# MCU_Headers.net
KiCad netlist of a schematic drawn in Altium Designer
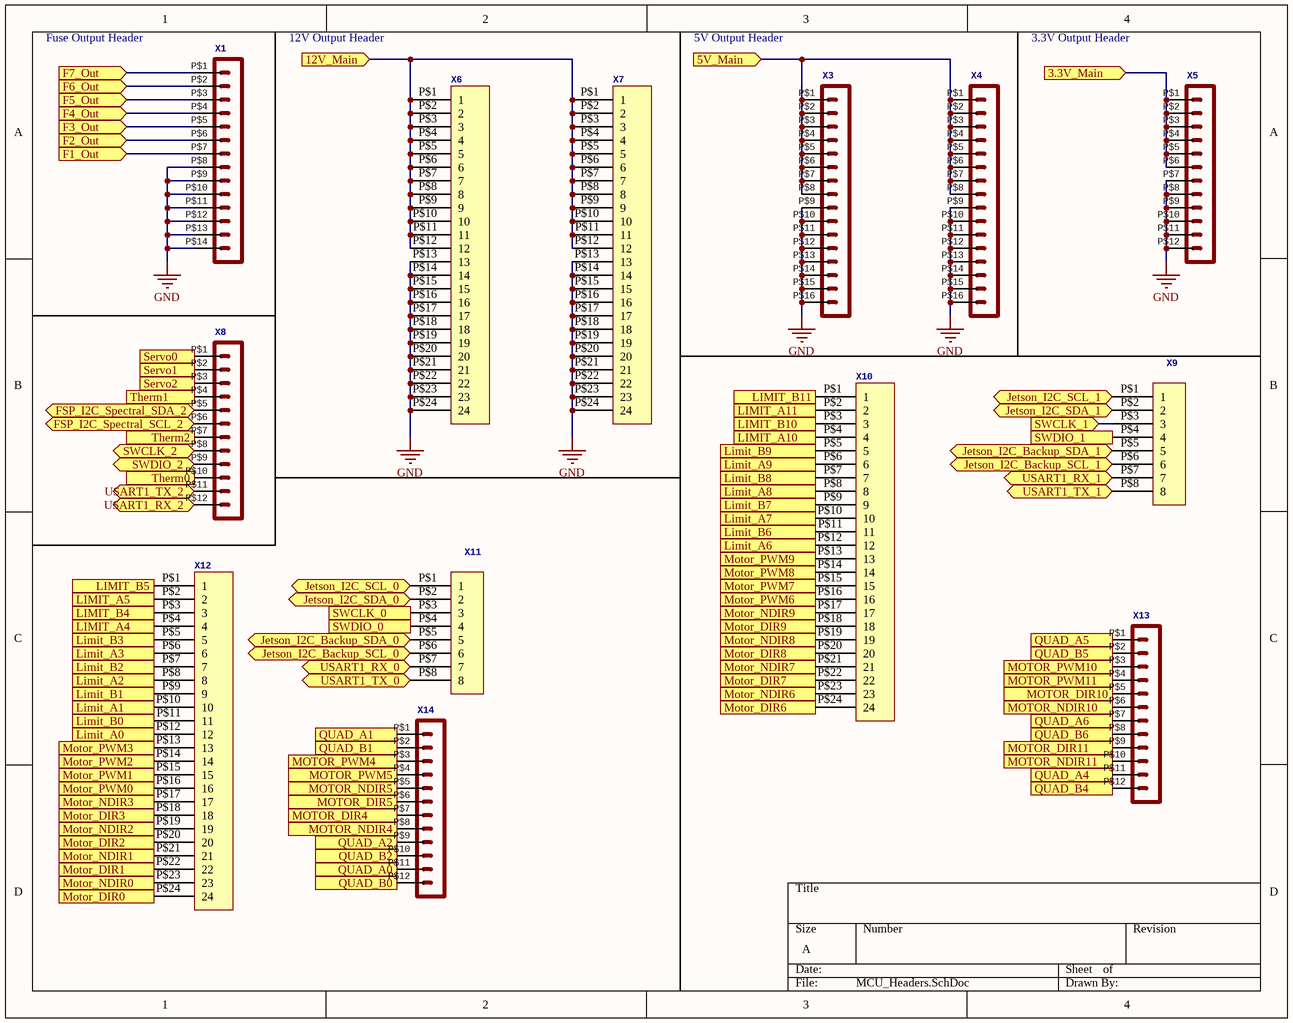
[diagram p0: MCU_Headers.SchDoc]

(export (version "E")
  (design (tool "Eeschema 10.0.6"))
  (components
    (comp (ref "X1")
      (value "Molex - Micro-Fit 3.0 Series connector,  3.00mm (0.118\") pitch header, 14 positions.")
      (footprint "43045-1412")
      (libsource (lib "Molex Microfit") (part "HEADER_POS14_?43045-1412"))
    )
    (comp (ref "X3")
      (value "Molex - Micro-Fit 3.0 Series connector,  3.00mm (0.118\") pitch header, 16 positions.")
      (footprint "43045-1612")
      (libsource (lib "Molex Microfit") (part "HEADER_POS16_?43045-1612"))
    )
    (comp (ref "X4")
      (value "Molex - Micro-Fit 3.0 Series connector,  3.00mm (0.118\") pitch header, 16 positions.")
      (footprint "43045-1612")
      (libsource (lib "Molex Microfit") (part "HEADER_POS16_?43045-1612"))
    )
    (comp (ref "X5")
      (value "Molex - Micro-Fit 3.0 Series connector,  3.00mm (0.118\") pitch header, 12 positions.")
      (footprint "43045-1212")
      (libsource (lib "Molex Microfit") (part "HEADER_POS12_?43045-1212"))
    )
    (comp (ref "X6")
      (value "Molex 43045-2412")
      (footprint "43045-2412")
      (libsource (lib "Molex Microfit") (part "Micro-Fit Molex 24 Pin Vertical"))
    )
    (comp (ref "X7")
      (value "Molex 43045-2412")
      (footprint "43045-2412")
      (libsource (lib "Molex Microfit") (part "Micro-Fit Molex 24 Pin Vertical"))
    )
    (comp (ref "X8")
      (value "Molex - Micro-Fit 3.0 Series connector,  3.00mm (0.118\") pitch header, 12 positions.")
      (footprint "43045-1212")
      (libsource (lib "Molex Microfit") (part "HEADER_POS12_?43045-1212"))
    )
    (comp (ref "X9")
      (value "Molex 43045-0812")
      (footprint "43045-0812")
      (libsource (lib "Molex Microfit") (part "Micro-Fit Molex 8 Pin 2 Row Vertical"))
    )
    (comp (ref "X10")
      (value "Molex 43045-2412")
      (footprint "43045-2412")
      (libsource (lib "Molex Microfit") (part "Micro-Fit Molex 24 Pin Vertical"))
    )
    (comp (ref "X11")
      (value "Molex 43045-0812")
      (footprint "43045-0812")
      (libsource (lib "Molex Microfit") (part "Micro-Fit Molex 8 Pin 2 Row Vertical"))
    )
    (comp (ref "X12")
      (value "Molex 43045-2412")
      (footprint "43045-2412")
      (libsource (lib "Molex Microfit") (part "Micro-Fit Molex 24 Pin Vertical"))
    )
    (comp (ref "X13")
      (value "Molex - Micro-Fit 3.0 Series connector,  3.00mm (0.118\") pitch header, 12 positions.")
      (footprint "43045-1212")
      (libsource (lib "Molex Microfit") (part "HEADER_POS12_?43045-1212"))
    )
    (comp (ref "X14")
      (value "Molex - Micro-Fit 3.0 Series connector,  3.00mm (0.118\") pitch header, 12 positions.")
      (footprint "43045-1212")
      (libsource (lib "Molex Microfit") (part "HEADER_POS12_?43045-1212"))
    )
  )
  (nets
    (net (code "1") (name "/3.3V_Main") (class "Default")
      (node (ref "X5") (pin "P$1") (pinfunction "1_P$1") (pintype "passive"))
      (node (ref "X5") (pin "P$2") (pinfunction "2_P$2") (pintype "passive"))
      (node (ref "X5") (pin "P$3") (pinfunction "3_P$3") (pintype "passive"))
      (node (ref "X5") (pin "P$4") (pinfunction "4_P$4") (pintype "passive"))
      (node (ref "X5") (pin "P$5") (pinfunction "5_P$5") (pintype "passive"))
      (node (ref "X5") (pin "P$6") (pinfunction "6_P$6") (pintype "passive"))
    )
    (net (code "2") (name "/5V_Main") (class "Default")
      (node (ref "X3") (pin "P$1") (pinfunction "1_P$1") (pintype "passive"))
      (node (ref "X3") (pin "P$2") (pinfunction "2_P$2") (pintype "passive"))
      (node (ref "X3") (pin "P$3") (pinfunction "3_P$3") (pintype "passive"))
      (node (ref "X3") (pin "P$4") (pinfunction "4_P$4") (pintype "passive"))
      (node (ref "X3") (pin "P$5") (pinfunction "5_P$5") (pintype "passive"))
      (node (ref "X3") (pin "P$6") (pinfunction "6_P$6") (pintype "passive"))
      (node (ref "X3") (pin "P$7") (pinfunction "7_P$7") (pintype "passive"))
      (node (ref "X3") (pin "P$8") (pinfunction "8_P$8") (pintype "passive"))
      (node (ref "X4") (pin "P$1") (pinfunction "1_P$1") (pintype "passive"))
      (node (ref "X4") (pin "P$2") (pinfunction "2_P$2") (pintype "passive"))
      (node (ref "X4") (pin "P$3") (pinfunction "3_P$3") (pintype "passive"))
      (node (ref "X4") (pin "P$4") (pinfunction "4_P$4") (pintype "passive"))
      (node (ref "X4") (pin "P$5") (pinfunction "5_P$5") (pintype "passive"))
      (node (ref "X4") (pin "P$6") (pinfunction "6_P$6") (pintype "passive"))
      (node (ref "X4") (pin "P$7") (pinfunction "7_P$7") (pintype "passive"))
      (node (ref "X4") (pin "P$8") (pinfunction "8_P$8") (pintype "passive"))
    )
    (net (code "3") (name "/12V_Main") (class "Default")
      (node (ref "X6") (pin "P$1") (pinfunction "1_P$1") (pintype "passive"))
      (node (ref "X6") (pin "P$10") (pinfunction "10_P$10") (pintype "passive"))
      (node (ref "X6") (pin "P$11") (pinfunction "11_P$11") (pintype "passive"))
      (node (ref "X6") (pin "P$12") (pinfunction "12_P$12") (pintype "passive"))
      (node (ref "X6") (pin "P$2") (pinfunction "2_P$2") (pintype "passive"))
      (node (ref "X6") (pin "P$3") (pinfunction "3_P$3") (pintype "passive"))
      (node (ref "X6") (pin "P$4") (pinfunction "4_P$4") (pintype "passive"))
      (node (ref "X6") (pin "P$5") (pinfunction "5_P$5") (pintype "passive"))
      (node (ref "X6") (pin "P$6") (pinfunction "6_P$6") (pintype "passive"))
      (node (ref "X6") (pin "P$7") (pinfunction "7_P$7") (pintype "passive"))
      (node (ref "X6") (pin "P$8") (pinfunction "8_P$8") (pintype "passive"))
      (node (ref "X6") (pin "P$9") (pinfunction "9_P$9") (pintype "passive"))
      (node (ref "X7") (pin "P$1") (pinfunction "1_P$1") (pintype "passive"))
      (node (ref "X7") (pin "P$10") (pinfunction "10_P$10") (pintype "passive"))
      (node (ref "X7") (pin "P$11") (pinfunction "11_P$11") (pintype "passive"))
      (node (ref "X7") (pin "P$12") (pinfunction "12_P$12") (pintype "passive"))
      (node (ref "X7") (pin "P$2") (pinfunction "2_P$2") (pintype "passive"))
      (node (ref "X7") (pin "P$3") (pinfunction "3_P$3") (pintype "passive"))
      (node (ref "X7") (pin "P$4") (pinfunction "4_P$4") (pintype "passive"))
      (node (ref "X7") (pin "P$5") (pinfunction "5_P$5") (pintype "passive"))
      (node (ref "X7") (pin "P$6") (pinfunction "6_P$6") (pintype "passive"))
      (node (ref "X7") (pin "P$7") (pinfunction "7_P$7") (pintype "passive"))
      (node (ref "X7") (pin "P$8") (pinfunction "8_P$8") (pintype "passive"))
      (node (ref "X7") (pin "P$9") (pinfunction "9_P$9") (pintype "passive"))
    )
    (net (code "4") (name "/F1_Out") (class "Default")
      (node (ref "X1") (pin "P$7") (pinfunction "7_P$7") (pintype "passive"))
    )
    (net (code "5") (name "/F2_Out") (class "Default")
      (node (ref "X1") (pin "P$6") (pinfunction "6_P$6") (pintype "passive"))
    )
    (net (code "6") (name "/F3_Out") (class "Default")
      (node (ref "X1") (pin "P$5") (pinfunction "5_P$5") (pintype "passive"))
    )
    (net (code "7") (name "/F4_Out") (class "Default")
      (node (ref "X1") (pin "P$4") (pinfunction "4_P$4") (pintype "passive"))
    )
    (net (code "8") (name "/F5_Out") (class "Default")
      (node (ref "X1") (pin "P$3") (pinfunction "3_P$3") (pintype "passive"))
    )
    (net (code "9") (name "/F6_Out") (class "Default")
      (node (ref "X1") (pin "P$2") (pinfunction "2_P$2") (pintype "passive"))
    )
    (net (code "10") (name "/F7_Out") (class "Default")
      (node (ref "X1") (pin "P$1") (pinfunction "1_P$1") (pintype "passive"))
    )
    (net (code "11") (name "/FSP_I2C_Spectral_SCL_2") (class "Default")
      (node (ref "X8") (pin "P$6") (pinfunction "6_P$6") (pintype "passive"))
    )
    (net (code "12") (name "/FSP_I2C_Spectral_SDA_2") (class "Default")
      (node (ref "X8") (pin "P$5") (pinfunction "5_P$5") (pintype "passive"))
    )
    (net (code "13") (name "/Jetson_I2C_Backup_SCL_0") (class "Default")
      (node (ref "X11") (pin "P$6") (pinfunction "6_P$6") (pintype "passive"))
    )
    (net (code "14") (name "/Jetson_I2C_Backup_SCL_1") (class "Default")
      (node (ref "X9") (pin "P$6") (pinfunction "6_P$6") (pintype "passive"))
    )
    (net (code "15") (name "/Jetson_I2C_Backup_SDA_0") (class "Default")
      (node (ref "X11") (pin "P$5") (pinfunction "5_P$5") (pintype "passive"))
    )
    (net (code "16") (name "/Jetson_I2C_Backup_SDA_1") (class "Default")
      (node (ref "X9") (pin "P$5") (pinfunction "5_P$5") (pintype "passive"))
    )
    (net (code "17") (name "/Jetson_I2C_SCL_0") (class "Default")
      (node (ref "X11") (pin "P$1") (pinfunction "1_P$1") (pintype "passive"))
    )
    (net (code "18") (name "/Jetson_I2C_SCL_1") (class "Default")
      (node (ref "X9") (pin "P$1") (pinfunction "1_P$1") (pintype "passive"))
    )
    (net (code "19") (name "/Jetson_I2C_SDA_0") (class "Default")
      (node (ref "X11") (pin "P$2") (pinfunction "2_P$2") (pintype "passive"))
    )
    (net (code "20") (name "/Jetson_I2C_SDA_1") (class "Default")
      (node (ref "X9") (pin "P$2") (pinfunction "2_P$2") (pintype "passive"))
    )
    (net (code "21") (name "/LIMIT_A4") (class "Default")
      (node (ref "X12") (pin "P$4") (pinfunction "4_P$4") (pintype "passive"))
    )
    (net (code "22") (name "/LIMIT_A5") (class "Default")
      (node (ref "X12") (pin "P$2") (pinfunction "2_P$2") (pintype "passive"))
    )
    (net (code "23") (name "/LIMIT_A10") (class "Default")
      (node (ref "X10") (pin "P$4") (pinfunction "4_P$4") (pintype "passive"))
    )
    (net (code "24") (name "/LIMIT_A11") (class "Default")
      (node (ref "X10") (pin "P$2") (pinfunction "2_P$2") (pintype "passive"))
    )
    (net (code "25") (name "/LIMIT_B4") (class "Default")
      (node (ref "X12") (pin "P$3") (pinfunction "3_P$3") (pintype "passive"))
    )
    (net (code "26") (name "/LIMIT_B5") (class "Default")
      (node (ref "X12") (pin "P$1") (pinfunction "1_P$1") (pintype "passive"))
    )
    (net (code "27") (name "/LIMIT_B10") (class "Default")
      (node (ref "X10") (pin "P$3") (pinfunction "3_P$3") (pintype "passive"))
    )
    (net (code "28") (name "/LIMIT_B11") (class "Default")
      (node (ref "X10") (pin "P$1") (pinfunction "1_P$1") (pintype "passive"))
    )
    (net (code "29") (name "/Limit_A0") (class "Default")
      (node (ref "X12") (pin "P$12") (pinfunction "12_P$12") (pintype "passive"))
    )
    (net (code "30") (name "/Limit_A1") (class "Default")
      (node (ref "X12") (pin "P$10") (pinfunction "10_P$10") (pintype "passive"))
    )
    (net (code "31") (name "/Limit_A2") (class "Default")
      (node (ref "X12") (pin "P$8") (pinfunction "8_P$8") (pintype "passive"))
    )
    (net (code "32") (name "/Limit_A3") (class "Default")
      (node (ref "X12") (pin "P$6") (pinfunction "6_P$6") (pintype "passive"))
    )
    (net (code "33") (name "/Limit_A6") (class "Default")
      (node (ref "X10") (pin "P$12") (pinfunction "12_P$12") (pintype "passive"))
    )
    (net (code "34") (name "/Limit_A7") (class "Default")
      (node (ref "X10") (pin "P$10") (pinfunction "10_P$10") (pintype "passive"))
    )
    (net (code "35") (name "/Limit_A8") (class "Default")
      (node (ref "X10") (pin "P$8") (pinfunction "8_P$8") (pintype "passive"))
    )
    (net (code "36") (name "/Limit_A9") (class "Default")
      (node (ref "X10") (pin "P$6") (pinfunction "6_P$6") (pintype "passive"))
    )
    (net (code "37") (name "/Limit_B0") (class "Default")
      (node (ref "X12") (pin "P$11") (pinfunction "11_P$11") (pintype "passive"))
    )
    (net (code "38") (name "/Limit_B1") (class "Default")
      (node (ref "X12") (pin "P$9") (pinfunction "9_P$9") (pintype "passive"))
    )
    (net (code "39") (name "/Limit_B2") (class "Default")
      (node (ref "X12") (pin "P$7") (pinfunction "7_P$7") (pintype "passive"))
    )
    (net (code "40") (name "/Limit_B3") (class "Default")
      (node (ref "X12") (pin "P$5") (pinfunction "5_P$5") (pintype "passive"))
    )
    (net (code "41") (name "/Limit_B6") (class "Default")
      (node (ref "X10") (pin "P$11") (pinfunction "11_P$11") (pintype "passive"))
    )
    (net (code "42") (name "/Limit_B7") (class "Default")
      (node (ref "X10") (pin "P$9") (pinfunction "9_P$9") (pintype "passive"))
    )
    (net (code "43") (name "/Limit_B8") (class "Default")
      (node (ref "X10") (pin "P$7") (pinfunction "7_P$7") (pintype "passive"))
    )
    (net (code "44") (name "/Limit_B9") (class "Default")
      (node (ref "X10") (pin "P$5") (pinfunction "5_P$5") (pintype "passive"))
    )
    (net (code "45") (name "/MOTOR_DIR4") (class "Default")
      (node (ref "X14") (pin "P$7") (pinfunction "7_P$7") (pintype "passive"))
    )
    (net (code "46") (name "/MOTOR_DIR5") (class "Default")
      (node (ref "X14") (pin "P$6") (pinfunction "6_P$6") (pintype "passive"))
    )
    (net (code "47") (name "/MOTOR_DIR10") (class "Default")
      (node (ref "X13") (pin "P$5") (pinfunction "5_P$5") (pintype "passive"))
    )
    (net (code "48") (name "/MOTOR_DIR11") (class "Default")
      (node (ref "X13") (pin "P$9") (pinfunction "9_P$9") (pintype "passive"))
    )
    (net (code "49") (name "/MOTOR_NDIR4") (class "Default")
      (node (ref "X14") (pin "P$8") (pinfunction "8_P$8") (pintype "passive"))
    )
    (net (code "50") (name "/MOTOR_NDIR5") (class "Default")
      (node (ref "X14") (pin "P$5") (pinfunction "5_P$5") (pintype "passive"))
    )
    (net (code "51") (name "/MOTOR_NDIR10") (class "Default")
      (node (ref "X13") (pin "P$6") (pinfunction "6_P$6") (pintype "passive"))
    )
    (net (code "52") (name "/MOTOR_NDIR11") (class "Default")
      (node (ref "X13") (pin "P$10") (pinfunction "10_P$10") (pintype "passive"))
    )
    (net (code "53") (name "/MOTOR_PWM4") (class "Default")
      (node (ref "X14") (pin "P$3") (pinfunction "3_P$3") (pintype "passive"))
    )
    (net (code "54") (name "/MOTOR_PWM5") (class "Default")
      (node (ref "X14") (pin "P$4") (pinfunction "4_P$4") (pintype "passive"))
    )
    (net (code "55") (name "/MOTOR_PWM10") (class "Default")
      (node (ref "X13") (pin "P$3") (pinfunction "3_P$3") (pintype "passive"))
    )
    (net (code "56") (name "/MOTOR_PWM11") (class "Default")
      (node (ref "X13") (pin "P$4") (pinfunction "4_P$4") (pintype "passive"))
    )
    (net (code "57") (name "/Motor_DIR0") (class "Default")
      (node (ref "X12") (pin "P$24") (pinfunction "24_P$24") (pintype "passive"))
    )
    (net (code "58") (name "/Motor_DIR1") (class "Default")
      (node (ref "X12") (pin "P$22") (pinfunction "22_P$22") (pintype "passive"))
    )
    (net (code "59") (name "/Motor_DIR2") (class "Default")
      (node (ref "X12") (pin "P$20") (pinfunction "20_P$20") (pintype "passive"))
    )
    (net (code "60") (name "/Motor_DIR3") (class "Default")
      (node (ref "X12") (pin "P$18") (pinfunction "18_P$18") (pintype "passive"))
    )
    (net (code "61") (name "/Motor_DIR6") (class "Default")
      (node (ref "X10") (pin "P$24") (pinfunction "24_P$24") (pintype "passive"))
    )
    (net (code "62") (name "/Motor_DIR7") (class "Default")
      (node (ref "X10") (pin "P$22") (pinfunction "22_P$22") (pintype "passive"))
    )
    (net (code "63") (name "/Motor_DIR8") (class "Default")
      (node (ref "X10") (pin "P$20") (pinfunction "20_P$20") (pintype "passive"))
    )
    (net (code "64") (name "/Motor_DIR9") (class "Default")
      (node (ref "X10") (pin "P$18") (pinfunction "18_P$18") (pintype "passive"))
    )
    (net (code "65") (name "/Motor_NDIR0") (class "Default")
      (node (ref "X12") (pin "P$23") (pinfunction "23_P$23") (pintype "passive"))
    )
    (net (code "66") (name "/Motor_NDIR1") (class "Default")
      (node (ref "X12") (pin "P$21") (pinfunction "21_P$21") (pintype "passive"))
    )
    (net (code "67") (name "/Motor_NDIR2") (class "Default")
      (node (ref "X12") (pin "P$19") (pinfunction "19_P$19") (pintype "passive"))
    )
    (net (code "68") (name "/Motor_NDIR3") (class "Default")
      (node (ref "X12") (pin "P$17") (pinfunction "17_P$17") (pintype "passive"))
    )
    (net (code "69") (name "/Motor_NDIR6") (class "Default")
      (node (ref "X10") (pin "P$23") (pinfunction "23_P$23") (pintype "passive"))
    )
    (net (code "70") (name "/Motor_NDIR7") (class "Default")
      (node (ref "X10") (pin "P$21") (pinfunction "21_P$21") (pintype "passive"))
    )
    (net (code "71") (name "/Motor_NDIR8") (class "Default")
      (node (ref "X10") (pin "P$19") (pinfunction "19_P$19") (pintype "passive"))
    )
    (net (code "72") (name "/Motor_NDIR9") (class "Default")
      (node (ref "X10") (pin "P$17") (pinfunction "17_P$17") (pintype "passive"))
    )
    (net (code "73") (name "/Motor_PWM0") (class "Default")
      (node (ref "X12") (pin "P$16") (pinfunction "16_P$16") (pintype "passive"))
    )
    (net (code "74") (name "/Motor_PWM1") (class "Default")
      (node (ref "X12") (pin "P$15") (pinfunction "15_P$15") (pintype "passive"))
    )
    (net (code "75") (name "/Motor_PWM2") (class "Default")
      (node (ref "X12") (pin "P$14") (pinfunction "14_P$14") (pintype "passive"))
    )
    (net (code "76") (name "/Motor_PWM3") (class "Default")
      (node (ref "X12") (pin "P$13") (pinfunction "13_P$13") (pintype "passive"))
    )
    (net (code "77") (name "/Motor_PWM6") (class "Default")
      (node (ref "X10") (pin "P$16") (pinfunction "16_P$16") (pintype "passive"))
    )
    (net (code "78") (name "/Motor_PWM7") (class "Default")
      (node (ref "X10") (pin "P$15") (pinfunction "15_P$15") (pintype "passive"))
    )
    (net (code "79") (name "/Motor_PWM8") (class "Default")
      (node (ref "X10") (pin "P$14") (pinfunction "14_P$14") (pintype "passive"))
    )
    (net (code "80") (name "/Motor_PWM9") (class "Default")
      (node (ref "X10") (pin "P$13") (pinfunction "13_P$13") (pintype "passive"))
    )
    (net (code "81") (name "/QUAD_A0") (class "Default")
      (node (ref "X14") (pin "P$11") (pinfunction "11_P$11") (pintype "passive"))
    )
    (net (code "82") (name "/QUAD_A1") (class "Default")
      (node (ref "X14") (pin "P$1") (pinfunction "1_P$1") (pintype "passive"))
    )
    (net (code "83") (name "/QUAD_A2") (class "Default")
      (node (ref "X14") (pin "P$9") (pinfunction "9_P$9") (pintype "passive"))
    )
    (net (code "84") (name "/QUAD_A4") (class "Default")
      (node (ref "X13") (pin "P$11") (pinfunction "11_P$11") (pintype "passive"))
    )
    (net (code "85") (name "/QUAD_A5") (class "Default")
      (node (ref "X13") (pin "P$1") (pinfunction "1_P$1") (pintype "passive"))
    )
    (net (code "86") (name "/QUAD_A6") (class "Default")
      (node (ref "X13") (pin "P$7") (pinfunction "7_P$7") (pintype "passive"))
    )
    (net (code "87") (name "/QUAD_B0") (class "Default")
      (node (ref "X14") (pin "P$12") (pinfunction "12_P$12") (pintype "passive"))
    )
    (net (code "88") (name "/QUAD_B1") (class "Default")
      (node (ref "X14") (pin "P$2") (pinfunction "2_P$2") (pintype "passive"))
    )
    (net (code "89") (name "/QUAD_B2") (class "Default")
      (node (ref "X14") (pin "P$10") (pinfunction "10_P$10") (pintype "passive"))
    )
    (net (code "90") (name "/QUAD_B4") (class "Default")
      (node (ref "X13") (pin "P$12") (pinfunction "12_P$12") (pintype "passive"))
    )
    (net (code "91") (name "/QUAD_B5") (class "Default")
      (node (ref "X13") (pin "P$2") (pinfunction "2_P$2") (pintype "passive"))
    )
    (net (code "92") (name "/QUAD_B6") (class "Default")
      (node (ref "X13") (pin "P$8") (pinfunction "8_P$8") (pintype "passive"))
    )
    (net (code "93") (name "/SWCLK_0") (class "Default")
      (node (ref "X11") (pin "P$3") (pinfunction "3_P$3") (pintype "passive"))
    )
    (net (code "94") (name "/SWCLK_1") (class "Default")
      (node (ref "X9") (pin "P$3") (pinfunction "3_P$3") (pintype "passive"))
    )
    (net (code "95") (name "/SWCLK_2") (class "Default")
      (node (ref "X8") (pin "P$8") (pinfunction "8_P$8") (pintype "passive"))
    )
    (net (code "96") (name "/SWDIO_0") (class "Default")
      (node (ref "X11") (pin "P$4") (pinfunction "4_P$4") (pintype "passive"))
    )
    (net (code "97") (name "/SWDIO_1") (class "Default")
      (node (ref "X9") (pin "P$4") (pinfunction "4_P$4") (pintype "passive"))
    )
    (net (code "98") (name "/SWDIO_2") (class "Default")
      (node (ref "X8") (pin "P$9") (pinfunction "9_P$9") (pintype "passive"))
    )
    (net (code "99") (name "/Servo0") (class "Default")
      (node (ref "X8") (pin "P$1") (pinfunction "1_P$1") (pintype "passive"))
    )
    (net (code "100") (name "/Servo1") (class "Default")
      (node (ref "X8") (pin "P$2") (pinfunction "2_P$2") (pintype "passive"))
    )
    (net (code "101") (name "/Servo2") (class "Default")
      (node (ref "X8") (pin "P$3") (pinfunction "3_P$3") (pintype "passive"))
    )
    (net (code "102") (name "/Therm0") (class "Default")
      (node (ref "X8") (pin "P$10") (pinfunction "10_P$10") (pintype "passive"))
    )
    (net (code "103") (name "/Therm1") (class "Default")
      (node (ref "X8") (pin "P$4") (pinfunction "4_P$4") (pintype "passive"))
    )
    (net (code "104") (name "/Therm2") (class "Default")
      (node (ref "X8") (pin "P$7") (pinfunction "7_P$7") (pintype "passive"))
    )
    (net (code "105") (name "/USART1_RX_0") (class "Default")
      (node (ref "X11") (pin "P$7") (pinfunction "7_P$7") (pintype "passive"))
    )
    (net (code "106") (name "/USART1_RX_1") (class "Default")
      (node (ref "X9") (pin "P$7") (pinfunction "7_P$7") (pintype "passive"))
    )
    (net (code "107") (name "/USART1_RX_2") (class "Default")
      (node (ref "X8") (pin "P$12") (pinfunction "12_P$12") (pintype "passive"))
    )
    (net (code "108") (name "/USART1_TX_0") (class "Default")
      (node (ref "X11") (pin "P$8") (pinfunction "8_P$8") (pintype "passive"))
    )
    (net (code "109") (name "/USART1_TX_1") (class "Default")
      (node (ref "X9") (pin "P$8") (pinfunction "8_P$8") (pintype "passive"))
    )
    (net (code "110") (name "/USART1_TX_2") (class "Default")
      (node (ref "X8") (pin "P$11") (pinfunction "11_P$11") (pintype "passive"))
    )
    (net (code "111") (name "GND") (class "Default")
      (node (ref "X1") (pin "P$10") (pinfunction "10_P$10") (pintype "passive"))
      (node (ref "X1") (pin "P$11") (pinfunction "11_P$11") (pintype "passive"))
      (node (ref "X1") (pin "P$12") (pinfunction "12_P$12") (pintype "passive"))
      (node (ref "X1") (pin "P$13") (pinfunction "13_P$13") (pintype "passive"))
      (node (ref "X1") (pin "P$14") (pinfunction "14_P$14") (pintype "passive"))
      (node (ref "X1") (pin "P$8") (pinfunction "8_P$8") (pintype "passive"))
      (node (ref "X1") (pin "P$9") (pinfunction "9_P$9") (pintype "passive"))
      (node (ref "X3") (pin "P$10") (pinfunction "10_P$10") (pintype "passive"))
      (node (ref "X3") (pin "P$11") (pinfunction "11_P$11") (pintype "passive"))
      (node (ref "X3") (pin "P$12") (pinfunction "12_P$12") (pintype "passive"))
      (node (ref "X3") (pin "P$13") (pinfunction "13_P$13") (pintype "passive"))
      (node (ref "X3") (pin "P$14") (pinfunction "14_P$14") (pintype "passive"))
      (node (ref "X3") (pin "P$15") (pinfunction "15_P$15") (pintype "passive"))
      (node (ref "X3") (pin "P$16") (pinfunction "16_P$16") (pintype "passive"))
      (node (ref "X3") (pin "P$9") (pinfunction "9_P$9") (pintype "passive"))
      (node (ref "X4") (pin "P$10") (pinfunction "10_P$10") (pintype "passive"))
      (node (ref "X4") (pin "P$11") (pinfunction "11_P$11") (pintype "passive"))
      (node (ref "X4") (pin "P$12") (pinfunction "12_P$12") (pintype "passive"))
      (node (ref "X4") (pin "P$13") (pinfunction "13_P$13") (pintype "passive"))
      (node (ref "X4") (pin "P$14") (pinfunction "14_P$14") (pintype "passive"))
      (node (ref "X4") (pin "P$15") (pinfunction "15_P$15") (pintype "passive"))
      (node (ref "X4") (pin "P$16") (pinfunction "16_P$16") (pintype "passive"))
      (node (ref "X4") (pin "P$9") (pinfunction "9_P$9") (pintype "passive"))
      (node (ref "X5") (pin "P$10") (pinfunction "10_P$10") (pintype "passive"))
      (node (ref "X5") (pin "P$11") (pinfunction "11_P$11") (pintype "passive"))
      (node (ref "X5") (pin "P$12") (pinfunction "12_P$12") (pintype "passive"))
      (node (ref "X5") (pin "P$7") (pinfunction "7_P$7") (pintype "passive"))
      (node (ref "X5") (pin "P$8") (pinfunction "8_P$8") (pintype "passive"))
      (node (ref "X5") (pin "P$9") (pinfunction "9_P$9") (pintype "passive"))
      (node (ref "X6") (pin "P$13") (pinfunction "13_P$13") (pintype "passive"))
      (node (ref "X6") (pin "P$14") (pinfunction "14_P$14") (pintype "passive"))
      (node (ref "X6") (pin "P$15") (pinfunction "15_P$15") (pintype "passive"))
      (node (ref "X6") (pin "P$16") (pinfunction "16_P$16") (pintype "passive"))
      (node (ref "X6") (pin "P$17") (pinfunction "17_P$17") (pintype "passive"))
      (node (ref "X6") (pin "P$18") (pinfunction "18_P$18") (pintype "passive"))
      (node (ref "X6") (pin "P$19") (pinfunction "19_P$19") (pintype "passive"))
      (node (ref "X6") (pin "P$20") (pinfunction "20_P$20") (pintype "passive"))
      (node (ref "X6") (pin "P$21") (pinfunction "21_P$21") (pintype "passive"))
      (node (ref "X6") (pin "P$22") (pinfunction "22_P$22") (pintype "passive"))
      (node (ref "X6") (pin "P$23") (pinfunction "23_P$23") (pintype "passive"))
      (node (ref "X6") (pin "P$24") (pinfunction "24_P$24") (pintype "passive"))
      (node (ref "X7") (pin "P$13") (pinfunction "13_P$13") (pintype "passive"))
      (node (ref "X7") (pin "P$14") (pinfunction "14_P$14") (pintype "passive"))
      (node (ref "X7") (pin "P$15") (pinfunction "15_P$15") (pintype "passive"))
      (node (ref "X7") (pin "P$16") (pinfunction "16_P$16") (pintype "passive"))
      (node (ref "X7") (pin "P$17") (pinfunction "17_P$17") (pintype "passive"))
      (node (ref "X7") (pin "P$18") (pinfunction "18_P$18") (pintype "passive"))
      (node (ref "X7") (pin "P$19") (pinfunction "19_P$19") (pintype "passive"))
      (node (ref "X7") (pin "P$20") (pinfunction "20_P$20") (pintype "passive"))
      (node (ref "X7") (pin "P$21") (pinfunction "21_P$21") (pintype "passive"))
      (node (ref "X7") (pin "P$22") (pinfunction "22_P$22") (pintype "passive"))
      (node (ref "X7") (pin "P$23") (pinfunction "23_P$23") (pintype "passive"))
      (node (ref "X7") (pin "P$24") (pinfunction "24_P$24") (pintype "passive"))
    )
  )
)
